# tiltcontrol.net
KiCad netlist of a schematic drawn in EAGLE
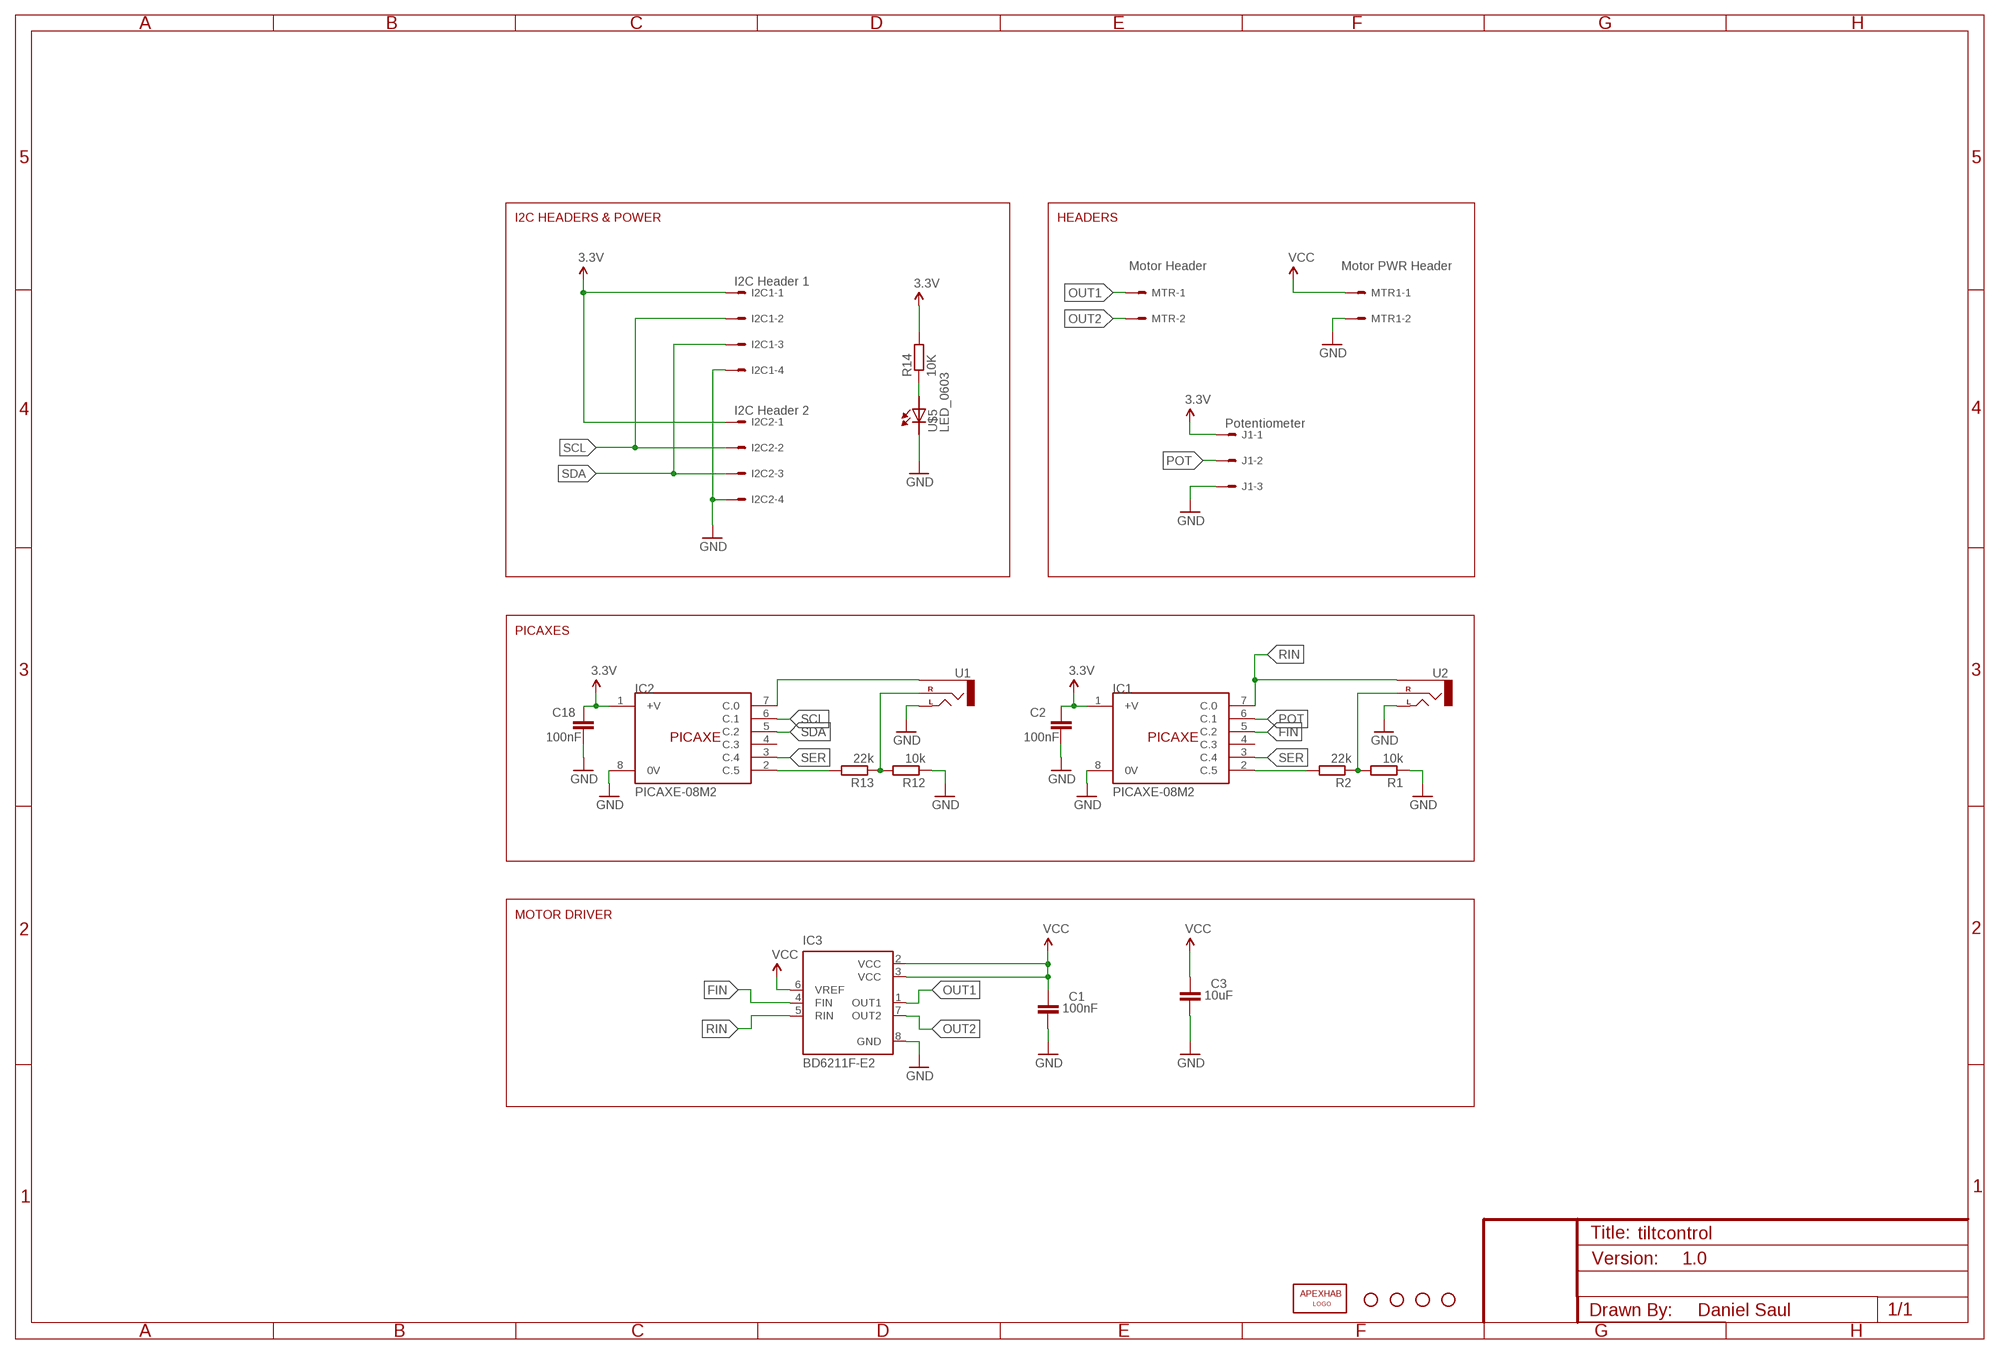
[diagram p0: schematic, sheet 1]

(export (version "E")
  (design (tool "Eeschema 10.0.6"))
  (components
    (comp (ref "C1")
      (value "100nF")
      (footprint "eagle-import:C0805")
      (libsource (lib "eagle-import") (part "C-EUC0805"))
    )
    (comp (ref "C2")
      (value "100nF")
      (footprint "eagle-import:C0805")
      (libsource (lib "eagle-import") (part "C-EUC0805"))
    )
    (comp (ref "C3")
      (value "10uF")
      (footprint "eagle-import:C0805")
      (libsource (lib "eagle-import") (part "C-EUC0805"))
    )
    (comp (ref "C18")
      (value "100nF")
      (footprint "eagle-import:C0805")
      (libsource (lib "eagle-import") (part "C-EUC0805"))
    )
    (comp (ref "I2C1")
      (value "I2C Header 1")
      (footprint "eagle-import:6410-04")
      (libsource (lib "eagle-import") (part "22-?-0427-2041"))
    )
    (comp (ref "I2C2")
      (value "I2C Header 2")
      (footprint "eagle-import:6410-04")
      (libsource (lib "eagle-import") (part "22-?-0427-2041"))
    )
    (comp (ref "IC1")
      (value "PICAXE-08M2")
      (footprint "eagle-import:SOIC8")
      (libsource (lib "eagle-import") (part "PICAXE-08M2"))
    )
    (comp (ref "IC2")
      (value "PICAXE-08M2")
      (footprint "eagle-import:SOIC8")
      (libsource (lib "eagle-import") (part "PICAXE-08M2"))
    )
    (comp (ref "IC3")
      (value "BD6211F-E2")
      (footprint "eagle-import:SOP8")
      (fields (field (name "MPN") "BD6230F-E2"))
      (libsource (lib "eagle-import") (part "BD623F0"))
    )
    (comp (ref "J1")
      (value "Potentiometer")
      (footprint "eagle-import:6410-03")
      (libsource (lib "eagle-import") (part "22-?-0327-2031"))
    )
    (comp (ref "JP1")
      (value "APEXHAB-LOGO_APEXHAB-SMALL")
      (footprint "eagle-import:APEXHAB-LOGO-SMALL")
      (libsource (lib "eagle-import") (part "APEXHAB-LOGO_APEXHAB-SMALL"))
    )
    (comp (ref "JP2")
      (value "STAND-OFF")
      (footprint "eagle-import:STAND-OFF")
      (libsource (lib "eagle-import") (part "STAND-OFF"))
    )
    (comp (ref "JP3")
      (value "STAND-OFF")
      (footprint "eagle-import:STAND-OFF")
      (libsource (lib "eagle-import") (part "STAND-OFF"))
    )
    (comp (ref "JP4")
      (value "STAND-OFF")
      (footprint "eagle-import:STAND-OFF")
      (libsource (lib "eagle-import") (part "STAND-OFF"))
    )
    (comp (ref "JP5")
      (value "STAND-OFF")
      (footprint "eagle-import:STAND-OFF")
      (libsource (lib "eagle-import") (part "STAND-OFF"))
    )
    (comp (ref "MTR")
      (value "Motor Header")
      (footprint "eagle-import:6410-02")
      (libsource (lib "eagle-import") (part "22-?-0227-2021"))
    )
    (comp (ref "MTR1")
      (value "Motor PWR Header")
      (footprint "eagle-import:6410-02")
      (libsource (lib "eagle-import") (part "22-?-0227-2021"))
    )
    (comp (ref "R1")
      (value "10k")
      (footprint "eagle-import:R0805")
      (libsource (lib "eagle-import") (part "R-EU_R0805"))
    )
    (comp (ref "R2")
      (value "22k")
      (footprint "eagle-import:R0805")
      (libsource (lib "eagle-import") (part "R-EU_R0805"))
    )
    (comp (ref "R12")
      (value "10k")
      (footprint "eagle-import:R0805")
      (libsource (lib "eagle-import") (part "R-EU_R0805"))
    )
    (comp (ref "R13")
      (value "22k")
      (footprint "eagle-import:R0805")
      (libsource (lib "eagle-import") (part "R-EU_R0805"))
    )
    (comp (ref "R14")
      (value "10K")
      (footprint "eagle-import:R0805")
      (libsource (lib "eagle-import") (part "R-EU_R0805"))
    )
    (comp (ref "U$5")
      (value "LED_0603")
      (footprint "eagle-import:CHIPLED_0603")
      (libsource (lib "eagle-import") (part "LED_0603"))
    )
    (comp (ref "U1")
      (value "AUDIO-JACKPTH")
      (footprint "eagle-import:AUDIO-JACK")
      (libsource (lib "eagle-import") (part "AUDIO-JACKPTH"))
    )
    (comp (ref "U2")
      (value "AUDIO-JACKPTH")
      (footprint "eagle-import:AUDIO-JACK")
      (libsource (lib "eagle-import") (part "AUDIO-JACKPTH"))
    )
  )
  (nets
    (net (code "1") (name "3.3V") (class "Default")
      (node (ref "C18") (pin "1") (pinfunction "1_1") (pintype "passive"))
      (node (ref "C2") (pin "1") (pinfunction "1_1") (pintype "passive"))
      (node (ref "I2C1") (pin "1") (pinfunction "S_1") (pintype "passive"))
      (node (ref "I2C2") (pin "1") (pinfunction "S_1") (pintype "passive"))
      (node (ref "IC1") (pin "1") (pinfunction "+V_1") (pintype "power_in"))
      (node (ref "IC2") (pin "1") (pinfunction "+V_1") (pintype "power_in"))
      (node (ref "J1") (pin "1") (pinfunction "S_1") (pintype "passive"))
      (node (ref "R14") (pin "2") (pinfunction "2_2") (pintype "passive"))
    )
    (net (code "2") (name "FIN") (class "Default")
      (node (ref "IC1") (pin "5") (pinfunction "C.2_5") (pintype "bidirectional"))
      (node (ref "IC3") (pin "4") (pinfunction "FIN_4") (pintype "input"))
    )
    (net (code "3") (name "GND") (class "Default")
      (node (ref "C1") (pin "2") (pinfunction "2_2") (pintype "passive"))
      (node (ref "C18") (pin "2") (pinfunction "2_2") (pintype "passive"))
      (node (ref "C2") (pin "2") (pinfunction "2_2") (pintype "passive"))
      (node (ref "C3") (pin "2") (pinfunction "2_2") (pintype "passive"))
      (node (ref "I2C1") (pin "4") (pinfunction "S_4") (pintype "passive"))
      (node (ref "I2C2") (pin "4") (pinfunction "S_4") (pintype "passive"))
      (node (ref "IC1") (pin "8") (pinfunction "0V_8") (pintype "power_in"))
      (node (ref "IC2") (pin "8") (pinfunction "0V_8") (pintype "power_in"))
      (node (ref "IC3") (pin "8") (pinfunction "GND_8") (pintype "power_in"))
      (node (ref "J1") (pin "3") (pinfunction "S_3") (pintype "passive"))
      (node (ref "MTR1") (pin "2") (pinfunction "S_2") (pintype "passive"))
      (node (ref "R1") (pin "1") (pinfunction "1_1") (pintype "passive"))
      (node (ref "R12") (pin "1") (pinfunction "1_1") (pintype "passive"))
      (node (ref "U$5") (pin "C") (pinfunction "C_C") (pintype "passive"))
      (node (ref "U1") (pin "TIP") (pinfunction "LEFT_TIP") (pintype "bidirectional"))
      (node (ref "U2") (pin "TIP") (pinfunction "LEFT_TIP") (pintype "bidirectional"))
    )
    (net (code "4") (name "Net-(IC1-C.5)") (class "Default")
      (node (ref "IC1") (pin "2") (pinfunction "C.5_2") (pintype "bidirectional"))
      (node (ref "R2") (pin "2") (pinfunction "2_2") (pintype "passive"))
    )
    (net (code "5") (name "Net-(IC2-C.0)") (class "Default")
      (node (ref "IC2") (pin "7") (pinfunction "C.0_7") (pintype "bidirectional"))
      (node (ref "U1") (pin "SLEEVE") (pinfunction "SLEEVE_SLEEVE") (pintype "bidirectional"))
    )
    (net (code "6") (name "Net-(IC2-C.5)") (class "Default")
      (node (ref "IC2") (pin "2") (pinfunction "C.5_2") (pintype "bidirectional"))
      (node (ref "R13") (pin "2") (pinfunction "2_2") (pintype "passive"))
    )
    (net (code "7") (name "Net-(R14-Pad1)") (class "Default")
      (node (ref "R14") (pin "1") (pinfunction "1_1") (pintype "passive"))
      (node (ref "U$5") (pin "A") (pinfunction "A_A") (pintype "passive"))
    )
    (net (code "8") (name "Net-(U1-RIGHT)") (class "Default")
      (node (ref "R12") (pin "2") (pinfunction "2_2") (pintype "passive"))
      (node (ref "R13") (pin "1") (pinfunction "1_1") (pintype "passive"))
      (node (ref "U1") (pin "RING") (pinfunction "RIGHT_RING") (pintype "bidirectional"))
    )
    (net (code "9") (name "Net-(U2-RIGHT)") (class "Default")
      (node (ref "R1") (pin "2") (pinfunction "2_2") (pintype "passive"))
      (node (ref "R2") (pin "1") (pinfunction "1_1") (pintype "passive"))
      (node (ref "U2") (pin "RING") (pinfunction "RIGHT_RING") (pintype "bidirectional"))
    )
    (net (code "10") (name "OUT1") (class "Default")
      (node (ref "IC3") (pin "1") (pinfunction "OUT1_1") (pintype "output"))
      (node (ref "MTR") (pin "1") (pinfunction "S_1") (pintype "passive"))
    )
    (net (code "11") (name "OUT2") (class "Default")
      (node (ref "IC3") (pin "7") (pinfunction "OUT2_7") (pintype "output"))
      (node (ref "MTR") (pin "2") (pinfunction "S_2") (pintype "passive"))
    )
    (net (code "12") (name "POT") (class "Default")
      (node (ref "IC1") (pin "6") (pinfunction "C.1_6") (pintype "bidirectional"))
      (node (ref "J1") (pin "2") (pinfunction "S_2") (pintype "passive"))
    )
    (net (code "13") (name "RIN") (class "Default")
      (node (ref "IC1") (pin "7") (pinfunction "C.0_7") (pintype "bidirectional"))
      (node (ref "IC3") (pin "5") (pinfunction "RIN_5") (pintype "input"))
      (node (ref "U2") (pin "SLEEVE") (pinfunction "SLEEVE_SLEEVE") (pintype "bidirectional"))
    )
    (net (code "14") (name "SCL") (class "Default")
      (node (ref "I2C1") (pin "2") (pinfunction "S_2") (pintype "passive"))
      (node (ref "I2C2") (pin "2") (pinfunction "S_2") (pintype "passive"))
      (node (ref "IC2") (pin "6") (pinfunction "C.1_6") (pintype "bidirectional"))
    )
    (net (code "15") (name "SDA") (class "Default")
      (node (ref "I2C1") (pin "3") (pinfunction "S_3") (pintype "passive"))
      (node (ref "I2C2") (pin "3") (pinfunction "S_3") (pintype "passive"))
      (node (ref "IC2") (pin "5") (pinfunction "C.2_5") (pintype "bidirectional"))
    )
    (net (code "16") (name "SER") (class "Default")
      (node (ref "IC1") (pin "3") (pinfunction "C.4_3") (pintype "bidirectional"))
      (node (ref "IC2") (pin "3") (pinfunction "C.4_3") (pintype "bidirectional"))
    )
    (net (code "17") (name "VCC") (class "Default")
      (node (ref "C1") (pin "1") (pinfunction "1_1") (pintype "passive"))
      (node (ref "C3") (pin "1") (pinfunction "1_1") (pintype "passive"))
      (node (ref "IC3") (pin "2") (pinfunction "VCC_2") (pintype "power_in"))
      (node (ref "IC3") (pin "3") (pinfunction "VCC_3") (pintype "power_in"))
      (node (ref "IC3") (pin "6") (pinfunction "VREF_6") (pintype "passive"))
      (node (ref "MTR1") (pin "1") (pinfunction "S_1") (pintype "passive"))
    )
    (net (code "18") (name "unconnected-(IC1-C.3-Pad4)") (class "Default")
      (node (ref "IC1") (pin "4") (pinfunction "C.3_4") (pintype "bidirectional"))
    )
    (net (code "19") (name "unconnected-(IC2-C.3-Pad4)") (class "Default")
      (node (ref "IC2") (pin "4") (pinfunction "C.3_4") (pintype "bidirectional"))
    )
  )
)
